# tester.net
KiCad netlist of a schematic drawn in EAGLE
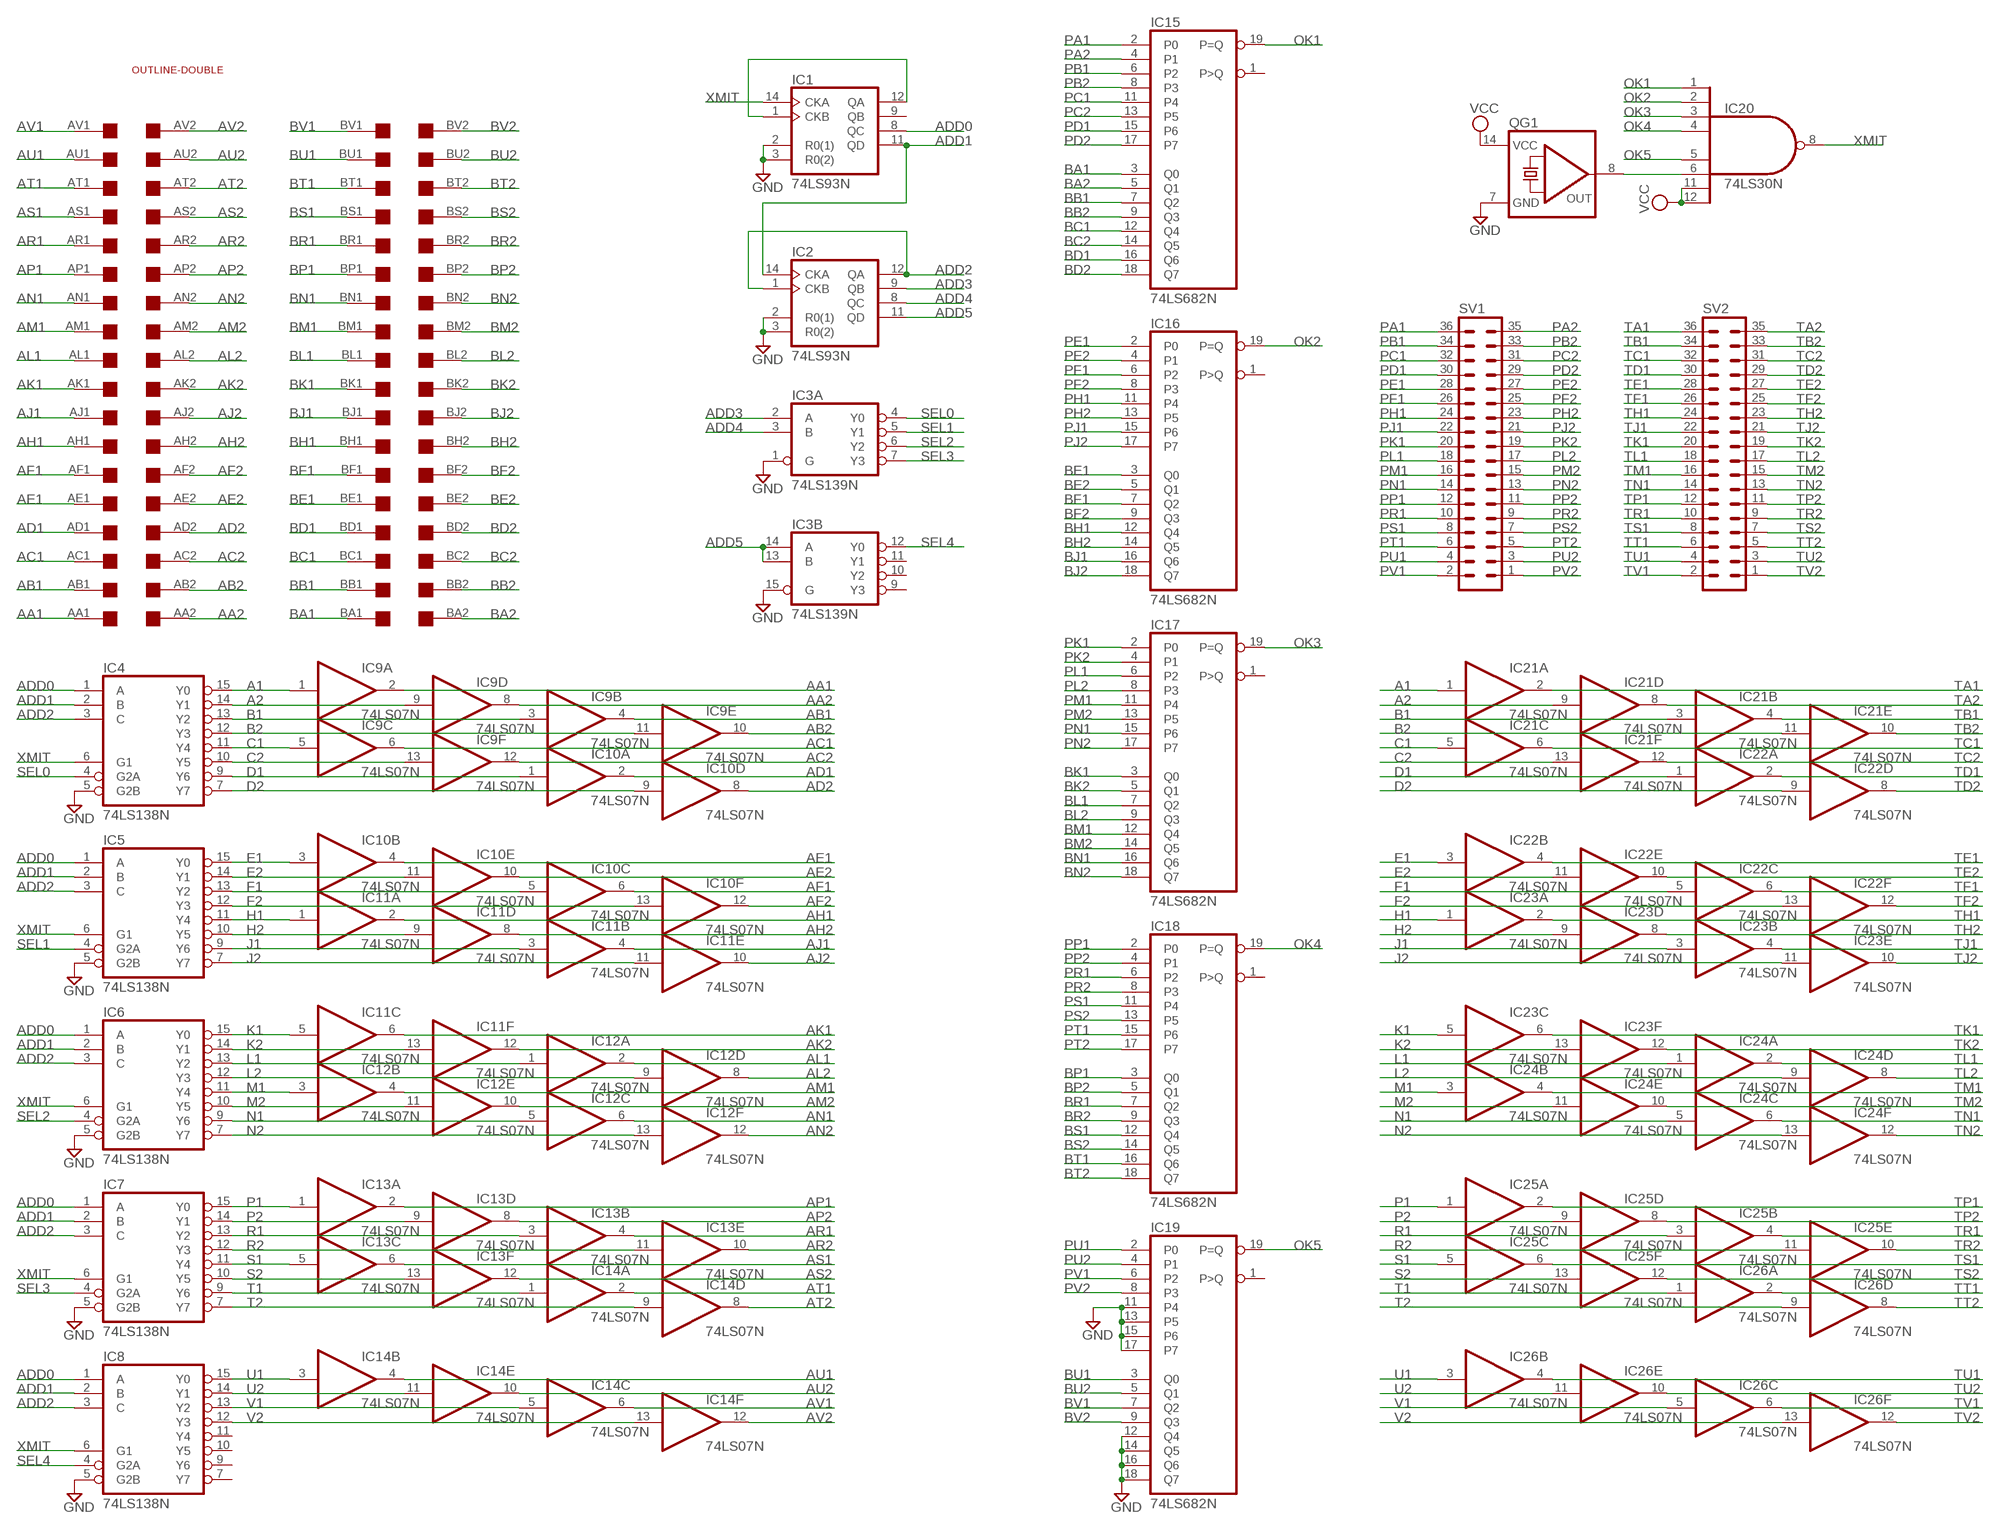
[diagram p0: schematic, sheet 1]

(export (version "E")
  (design (tool "Eeschema 10.0.6"))
  (components
    (comp (ref "IC1")
      (value "74LS93N")
      (footprint "eagle-import:DIL14")
      (libsource (lib "eagle-import") (part "7493NLS"))
    )
    (comp (ref "IC2")
      (value "74LS93N")
      (footprint "eagle-import:DIL14")
      (libsource (lib "eagle-import") (part "7493NLS"))
    )
    (comp (ref "IC3")
      (value "74LS139N")
      (footprint "eagle-import:DIL16")
      (libsource (lib "eagle-import") (part "74139NLS"))
    )
    (comp (ref "IC4")
      (value "74LS138N")
      (footprint "eagle-import:DIL16")
      (libsource (lib "eagle-import") (part "74138NLS"))
    )
    (comp (ref "IC5")
      (value "74LS138N")
      (footprint "eagle-import:DIL16")
      (libsource (lib "eagle-import") (part "74138NLS"))
    )
    (comp (ref "IC6")
      (value "74LS138N")
      (footprint "eagle-import:DIL16")
      (libsource (lib "eagle-import") (part "74138NLS"))
    )
    (comp (ref "IC7")
      (value "74LS138N")
      (footprint "eagle-import:DIL16")
      (libsource (lib "eagle-import") (part "74138NLS"))
    )
    (comp (ref "IC8")
      (value "74LS138N")
      (footprint "eagle-import:DIL16")
      (libsource (lib "eagle-import") (part "74138NLS"))
    )
    (comp (ref "IC9")
      (value "74LS07N")
      (footprint "eagle-import:DIL14")
      (libsource (lib "eagle-import") (part "7407NLS"))
    )
    (comp (ref "IC10")
      (value "74LS07N")
      (footprint "eagle-import:DIL14")
      (libsource (lib "eagle-import") (part "7407NLS"))
    )
    (comp (ref "IC11")
      (value "74LS07N")
      (footprint "eagle-import:DIL14")
      (libsource (lib "eagle-import") (part "7407NLS"))
    )
    (comp (ref "IC12")
      (value "74LS07N")
      (footprint "eagle-import:DIL14")
      (libsource (lib "eagle-import") (part "7407NLS"))
    )
    (comp (ref "IC13")
      (value "74LS07N")
      (footprint "eagle-import:DIL14")
      (libsource (lib "eagle-import") (part "7407NLS"))
    )
    (comp (ref "IC14")
      (value "74LS07N")
      (footprint "eagle-import:DIL14")
      (libsource (lib "eagle-import") (part "7407NLS"))
    )
    (comp (ref "IC15")
      (value "74LS682N")
      (footprint "eagle-import:DIL20")
      (libsource (lib "eagle-import") (part "74682NLS"))
    )
    (comp (ref "IC16")
      (value "74LS682N")
      (footprint "eagle-import:DIL20")
      (libsource (lib "eagle-import") (part "74682NLS"))
    )
    (comp (ref "IC17")
      (value "74LS682N")
      (footprint "eagle-import:DIL20")
      (libsource (lib "eagle-import") (part "74682NLS"))
    )
    (comp (ref "IC18")
      (value "74LS682N")
      (footprint "eagle-import:DIL20")
      (libsource (lib "eagle-import") (part "74682NLS"))
    )
    (comp (ref "IC19")
      (value "74LS682N")
      (footprint "eagle-import:DIL20")
      (libsource (lib "eagle-import") (part "74682NLS"))
    )
    (comp (ref "IC20")
      (value "74LS30N")
      (footprint "eagle-import:DIL14")
      (libsource (lib "eagle-import") (part "7430NLS"))
    )
    (comp (ref "IC21")
      (value "74LS07N")
      (footprint "eagle-import:DIL14")
      (libsource (lib "eagle-import") (part "7407NLS"))
    )
    (comp (ref "IC22")
      (value "74LS07N")
      (footprint "eagle-import:DIL14")
      (libsource (lib "eagle-import") (part "7407NLS"))
    )
    (comp (ref "IC23")
      (value "74LS07N")
      (footprint "eagle-import:DIL14")
      (libsource (lib "eagle-import") (part "7407NLS"))
    )
    (comp (ref "IC24")
      (value "74LS07N")
      (footprint "eagle-import:DIL14")
      (libsource (lib "eagle-import") (part "7407NLS"))
    )
    (comp (ref "IC25")
      (value "74LS07N")
      (footprint "eagle-import:DIL14")
      (libsource (lib "eagle-import") (part "7407NLS"))
    )
    (comp (ref "IC26")
      (value "74LS07N")
      (footprint "eagle-import:DIL14")
      (libsource (lib "eagle-import") (part "7407NLS"))
    )
    (comp (ref "QG1")
      (value "QG5860")
      (footprint "eagle-import:DIL14S")
      (libsource (lib "eagle-import") (part "QG5860"))
    )
    (comp (ref "SV1")
      (value "MA18-2")
      (footprint "eagle-import:MA18-2")
      (libsource (lib "eagle-import") (part "MA18-2"))
    )
    (comp (ref "SV2")
      (value "MA18-2")
      (footprint "eagle-import:MA18-2")
      (libsource (lib "eagle-import") (part "MA18-2"))
    )
    (comp (ref "U$1")
      (value "DOUBLE")
      (footprint "eagle-import:EDGE-CON4")
      (libsource (lib "eagle-import") (part "DOUBLE"))
    )
    (comp (ref "U$2")
      (value "OUTLINE-DOUBLE")
      (footprint "eagle-import:DOUBLE")
      (libsource (lib "eagle-import") (part "OUTLINE-DOUBLE"))
    )
  )
  (nets
    (net (code "1") (name "/A1") (class "Default")
      (node (ref "IC21") (pin "1") (pinfunction "I_1") (pintype "input"))
      (node (ref "IC4") (pin "15") (pinfunction "Y0_15") (pintype "output"))
      (node (ref "IC9") (pin "1") (pinfunction "I_1") (pintype "input"))
    )
    (net (code "2") (name "/A2") (class "Default")
      (node (ref "IC21") (pin "9") (pinfunction "I_9") (pintype "input"))
      (node (ref "IC4") (pin "14") (pinfunction "Y1_14") (pintype "output"))
      (node (ref "IC9") (pin "9") (pinfunction "I_9") (pintype "input"))
    )
    (net (code "3") (name "/AA1") (class "Default")
      (node (ref "IC9") (pin "2") (pinfunction "O_2") (pintype "open_collector"))
      (node (ref "U$1") (pin "AA1") (pinfunction "1_AA1") (pintype "bidirectional"))
    )
    (net (code "4") (name "/AA2") (class "Default")
      (node (ref "IC9") (pin "8") (pinfunction "O_8") (pintype "open_collector"))
      (node (ref "U$1") (pin "AA2") (pinfunction "1_AA2") (pintype "bidirectional"))
    )
    (net (code "5") (name "/AB1") (class "Default")
      (node (ref "IC9") (pin "4") (pinfunction "O_4") (pintype "open_collector"))
      (node (ref "U$1") (pin "AB1") (pinfunction "1_AB1") (pintype "bidirectional"))
    )
    (net (code "6") (name "/AB2") (class "Default")
      (node (ref "IC9") (pin "10") (pinfunction "O_10") (pintype "open_collector"))
      (node (ref "U$1") (pin "AB2") (pinfunction "1_AB2") (pintype "bidirectional"))
    )
    (net (code "7") (name "/AC1") (class "Default")
      (node (ref "IC9") (pin "6") (pinfunction "O_6") (pintype "open_collector"))
      (node (ref "U$1") (pin "AC1") (pinfunction "1_AC1") (pintype "bidirectional"))
    )
    (net (code "8") (name "/AC2") (class "Default")
      (node (ref "IC9") (pin "12") (pinfunction "O_12") (pintype "open_collector"))
      (node (ref "U$1") (pin "AC2") (pinfunction "1_AC2") (pintype "bidirectional"))
    )
    (net (code "9") (name "/AD1") (class "Default")
      (node (ref "IC10") (pin "2") (pinfunction "O_2") (pintype "open_collector"))
      (node (ref "U$1") (pin "AD1") (pinfunction "1_AD1") (pintype "bidirectional"))
    )
    (net (code "10") (name "/AD2") (class "Default")
      (node (ref "IC10") (pin "8") (pinfunction "O_8") (pintype "open_collector"))
      (node (ref "U$1") (pin "AD2") (pinfunction "1_AD2") (pintype "bidirectional"))
    )
    (net (code "11") (name "/ADD0") (class "Default")
      (node (ref "IC1") (pin "8") (pinfunction "QC_8") (pintype "output"))
      (node (ref "IC4") (pin "1") (pinfunction "A_1") (pintype "input"))
      (node (ref "IC5") (pin "1") (pinfunction "A_1") (pintype "input"))
      (node (ref "IC6") (pin "1") (pinfunction "A_1") (pintype "input"))
      (node (ref "IC7") (pin "1") (pinfunction "A_1") (pintype "input"))
      (node (ref "IC8") (pin "1") (pinfunction "A_1") (pintype "input"))
    )
    (net (code "12") (name "/ADD1") (class "Default")
      (node (ref "IC1") (pin "11") (pinfunction "QD_11") (pintype "output"))
      (node (ref "IC2") (pin "14") (pinfunction "CKA_14") (pintype "input"))
      (node (ref "IC4") (pin "2") (pinfunction "B_2") (pintype "input"))
      (node (ref "IC5") (pin "2") (pinfunction "B_2") (pintype "input"))
      (node (ref "IC6") (pin "2") (pinfunction "B_2") (pintype "input"))
      (node (ref "IC7") (pin "2") (pinfunction "B_2") (pintype "input"))
      (node (ref "IC8") (pin "2") (pinfunction "B_2") (pintype "input"))
    )
    (net (code "13") (name "/ADD2") (class "Default")
      (node (ref "IC2") (pin "1") (pinfunction "CKB_1") (pintype "input"))
      (node (ref "IC2") (pin "12") (pinfunction "QA_12") (pintype "output"))
      (node (ref "IC4") (pin "3") (pinfunction "C_3") (pintype "input"))
      (node (ref "IC5") (pin "3") (pinfunction "C_3") (pintype "input"))
      (node (ref "IC6") (pin "3") (pinfunction "C_3") (pintype "input"))
      (node (ref "IC7") (pin "3") (pinfunction "C_3") (pintype "input"))
      (node (ref "IC8") (pin "3") (pinfunction "C_3") (pintype "input"))
    )
    (net (code "14") (name "/ADD3") (class "Default")
      (node (ref "IC2") (pin "9") (pinfunction "QB_9") (pintype "output"))
      (node (ref "IC3") (pin "2") (pinfunction "A_2") (pintype "input"))
    )
    (net (code "15") (name "/ADD4") (class "Default")
      (node (ref "IC2") (pin "8") (pinfunction "QC_8") (pintype "output"))
      (node (ref "IC3") (pin "3") (pinfunction "B_3") (pintype "input"))
    )
    (net (code "16") (name "/ADD5") (class "Default")
      (node (ref "IC2") (pin "11") (pinfunction "QD_11") (pintype "output"))
      (node (ref "IC3") (pin "13") (pinfunction "B_13") (pintype "input"))
      (node (ref "IC3") (pin "14") (pinfunction "A_14") (pintype "input"))
    )
    (net (code "17") (name "/AE1") (class "Default")
      (node (ref "IC10") (pin "4") (pinfunction "O_4") (pintype "open_collector"))
      (node (ref "U$1") (pin "AE1") (pinfunction "1_AE1") (pintype "bidirectional"))
    )
    (net (code "18") (name "/AE2") (class "Default")
      (node (ref "IC10") (pin "10") (pinfunction "O_10") (pintype "open_collector"))
      (node (ref "U$1") (pin "AE2") (pinfunction "1_AE2") (pintype "bidirectional"))
    )
    (net (code "19") (name "/AF1") (class "Default")
      (node (ref "IC10") (pin "6") (pinfunction "O_6") (pintype "open_collector"))
      (node (ref "U$1") (pin "AF1") (pinfunction "1_AF1") (pintype "bidirectional"))
    )
    (net (code "20") (name "/AF2") (class "Default")
      (node (ref "IC10") (pin "12") (pinfunction "O_12") (pintype "open_collector"))
      (node (ref "U$1") (pin "AF2") (pinfunction "1_AF2") (pintype "bidirectional"))
    )
    (net (code "21") (name "/AH1") (class "Default")
      (node (ref "IC11") (pin "2") (pinfunction "O_2") (pintype "open_collector"))
      (node (ref "U$1") (pin "AH1") (pinfunction "1_AH1") (pintype "bidirectional"))
    )
    (net (code "22") (name "/AH2") (class "Default")
      (node (ref "IC11") (pin "8") (pinfunction "O_8") (pintype "open_collector"))
      (node (ref "U$1") (pin "AH2") (pinfunction "1_AH2") (pintype "bidirectional"))
    )
    (net (code "23") (name "/AJ1") (class "Default")
      (node (ref "IC11") (pin "4") (pinfunction "O_4") (pintype "open_collector"))
      (node (ref "U$1") (pin "AJ1") (pinfunction "1_AJ1") (pintype "bidirectional"))
    )
    (net (code "24") (name "/AJ2") (class "Default")
      (node (ref "IC11") (pin "10") (pinfunction "O_10") (pintype "open_collector"))
      (node (ref "U$1") (pin "AJ2") (pinfunction "1_AJ2") (pintype "bidirectional"))
    )
    (net (code "25") (name "/AK1") (class "Default")
      (node (ref "IC11") (pin "6") (pinfunction "O_6") (pintype "open_collector"))
      (node (ref "U$1") (pin "AK1") (pinfunction "1_AK1") (pintype "bidirectional"))
    )
    (net (code "26") (name "/AK2") (class "Default")
      (node (ref "IC11") (pin "12") (pinfunction "O_12") (pintype "open_collector"))
      (node (ref "U$1") (pin "AK2") (pinfunction "1_AK2") (pintype "bidirectional"))
    )
    (net (code "27") (name "/AL1") (class "Default")
      (node (ref "IC12") (pin "2") (pinfunction "O_2") (pintype "open_collector"))
      (node (ref "U$1") (pin "AL1") (pinfunction "1_AL1") (pintype "bidirectional"))
    )
    (net (code "28") (name "/AL2") (class "Default")
      (node (ref "IC12") (pin "8") (pinfunction "O_8") (pintype "open_collector"))
      (node (ref "U$1") (pin "AL2") (pinfunction "1_AL2") (pintype "bidirectional"))
    )
    (net (code "29") (name "/AM1") (class "Default")
      (node (ref "IC12") (pin "4") (pinfunction "O_4") (pintype "open_collector"))
      (node (ref "U$1") (pin "AM1") (pinfunction "1_AM1") (pintype "bidirectional"))
    )
    (net (code "30") (name "/AM2") (class "Default")
      (node (ref "IC12") (pin "10") (pinfunction "O_10") (pintype "open_collector"))
      (node (ref "U$1") (pin "AM2") (pinfunction "1_AM2") (pintype "bidirectional"))
    )
    (net (code "31") (name "/AN1") (class "Default")
      (node (ref "IC12") (pin "6") (pinfunction "O_6") (pintype "open_collector"))
      (node (ref "U$1") (pin "AN1") (pinfunction "1_AN1") (pintype "bidirectional"))
    )
    (net (code "32") (name "/AN2") (class "Default")
      (node (ref "IC12") (pin "12") (pinfunction "O_12") (pintype "open_collector"))
      (node (ref "U$1") (pin "AN2") (pinfunction "1_AN2") (pintype "bidirectional"))
    )
    (net (code "33") (name "/AP1") (class "Default")
      (node (ref "IC13") (pin "2") (pinfunction "O_2") (pintype "open_collector"))
      (node (ref "U$1") (pin "AP1") (pinfunction "1_AP1") (pintype "bidirectional"))
    )
    (net (code "34") (name "/AP2") (class "Default")
      (node (ref "IC13") (pin "8") (pinfunction "O_8") (pintype "open_collector"))
      (node (ref "U$1") (pin "AP2") (pinfunction "1_AP2") (pintype "bidirectional"))
    )
    (net (code "35") (name "/AR1") (class "Default")
      (node (ref "IC13") (pin "4") (pinfunction "O_4") (pintype "open_collector"))
      (node (ref "U$1") (pin "AR1") (pinfunction "1_AR1") (pintype "bidirectional"))
    )
    (net (code "36") (name "/AR2") (class "Default")
      (node (ref "IC13") (pin "10") (pinfunction "O_10") (pintype "open_collector"))
      (node (ref "U$1") (pin "AR2") (pinfunction "1_AR2") (pintype "bidirectional"))
    )
    (net (code "37") (name "/AS1") (class "Default")
      (node (ref "IC13") (pin "6") (pinfunction "O_6") (pintype "open_collector"))
      (node (ref "U$1") (pin "AS1") (pinfunction "1_AS1") (pintype "bidirectional"))
    )
    (net (code "38") (name "/AS2") (class "Default")
      (node (ref "IC13") (pin "12") (pinfunction "O_12") (pintype "open_collector"))
      (node (ref "U$1") (pin "AS2") (pinfunction "1_AS2") (pintype "bidirectional"))
    )
    (net (code "39") (name "/AT1") (class "Default")
      (node (ref "IC14") (pin "2") (pinfunction "O_2") (pintype "open_collector"))
      (node (ref "U$1") (pin "AT1") (pinfunction "1_AT1") (pintype "bidirectional"))
    )
    (net (code "40") (name "/AT2") (class "Default")
      (node (ref "IC14") (pin "8") (pinfunction "O_8") (pintype "open_collector"))
      (node (ref "U$1") (pin "AT2") (pinfunction "1_AT2") (pintype "bidirectional"))
    )
    (net (code "41") (name "/AU1") (class "Default")
      (node (ref "IC14") (pin "4") (pinfunction "O_4") (pintype "open_collector"))
      (node (ref "U$1") (pin "AU1") (pinfunction "1_AU1") (pintype "bidirectional"))
    )
    (net (code "42") (name "/AU2") (class "Default")
      (node (ref "IC14") (pin "10") (pinfunction "O_10") (pintype "open_collector"))
      (node (ref "U$1") (pin "AU2") (pinfunction "1_AU2") (pintype "bidirectional"))
    )
    (net (code "43") (name "/AV1") (class "Default")
      (node (ref "IC14") (pin "6") (pinfunction "O_6") (pintype "open_collector"))
      (node (ref "U$1") (pin "AV1") (pinfunction "1_AV1") (pintype "bidirectional"))
    )
    (net (code "44") (name "/AV2") (class "Default")
      (node (ref "IC14") (pin "12") (pinfunction "O_12") (pintype "open_collector"))
      (node (ref "U$1") (pin "AV2") (pinfunction "1_AV2") (pintype "bidirectional"))
    )
    (net (code "45") (name "/B1") (class "Default")
      (node (ref "IC21") (pin "3") (pinfunction "I_3") (pintype "input"))
      (node (ref "IC4") (pin "13") (pinfunction "Y2_13") (pintype "output"))
      (node (ref "IC9") (pin "3") (pinfunction "I_3") (pintype "input"))
    )
    (net (code "46") (name "/B2") (class "Default")
      (node (ref "IC21") (pin "11") (pinfunction "I_11") (pintype "input"))
      (node (ref "IC4") (pin "12") (pinfunction "Y3_12") (pintype "output"))
      (node (ref "IC9") (pin "11") (pinfunction "I_11") (pintype "input"))
    )
    (net (code "47") (name "/BA1") (class "Default")
      (node (ref "IC15") (pin "3") (pinfunction "Q0_3") (pintype "input"))
      (node (ref "U$1") (pin "BA1") (pinfunction "1_BA1") (pintype "bidirectional"))
    )
    (net (code "48") (name "/BA2") (class "Default")
      (node (ref "IC15") (pin "5") (pinfunction "Q1_5") (pintype "input"))
      (node (ref "U$1") (pin "BA2") (pinfunction "1_BA2") (pintype "bidirectional"))
    )
    (net (code "49") (name "/BB1") (class "Default")
      (node (ref "IC15") (pin "7") (pinfunction "Q2_7") (pintype "input"))
      (node (ref "U$1") (pin "BB1") (pinfunction "1_BB1") (pintype "bidirectional"))
    )
    (net (code "50") (name "/BB2") (class "Default")
      (node (ref "IC15") (pin "9") (pinfunction "Q3_9") (pintype "input"))
      (node (ref "U$1") (pin "BB2") (pinfunction "1_BB2") (pintype "bidirectional"))
    )
    (net (code "51") (name "/BC1") (class "Default")
      (node (ref "IC15") (pin "12") (pinfunction "Q4_12") (pintype "input"))
      (node (ref "U$1") (pin "BC1") (pinfunction "1_BC1") (pintype "bidirectional"))
    )
    (net (code "52") (name "/BC2") (class "Default")
      (node (ref "IC15") (pin "14") (pinfunction "Q5_14") (pintype "input"))
      (node (ref "U$1") (pin "BC2") (pinfunction "1_BC2") (pintype "bidirectional"))
    )
    (net (code "53") (name "/BD1") (class "Default")
      (node (ref "IC15") (pin "16") (pinfunction "Q6_16") (pintype "input"))
      (node (ref "U$1") (pin "BD1") (pinfunction "1_BD1") (pintype "bidirectional"))
    )
    (net (code "54") (name "/BD2") (class "Default")
      (node (ref "IC15") (pin "18") (pinfunction "Q7_18") (pintype "input"))
      (node (ref "U$1") (pin "BD2") (pinfunction "1_BD2") (pintype "bidirectional"))
    )
    (net (code "55") (name "/BE1") (class "Default")
      (node (ref "IC16") (pin "3") (pinfunction "Q0_3") (pintype "input"))
      (node (ref "U$1") (pin "BE1") (pinfunction "1_BE1") (pintype "bidirectional"))
    )
    (net (code "56") (name "/BE2") (class "Default")
      (node (ref "IC16") (pin "5") (pinfunction "Q1_5") (pintype "input"))
      (node (ref "U$1") (pin "BE2") (pinfunction "1_BE2") (pintype "bidirectional"))
    )
    (net (code "57") (name "/BF1") (class "Default")
      (node (ref "IC16") (pin "7") (pinfunction "Q2_7") (pintype "input"))
      (node (ref "U$1") (pin "BF1") (pinfunction "1_BF1") (pintype "bidirectional"))
    )
    (net (code "58") (name "/BF2") (class "Default")
      (node (ref "IC16") (pin "9") (pinfunction "Q3_9") (pintype "input"))
      (node (ref "U$1") (pin "BF2") (pinfunction "1_BF2") (pintype "bidirectional"))
    )
    (net (code "59") (name "/BH1") (class "Default")
      (node (ref "IC16") (pin "12") (pinfunction "Q4_12") (pintype "input"))
      (node (ref "U$1") (pin "BH1") (pinfunction "1_BH1") (pintype "bidirectional"))
    )
    (net (code "60") (name "/BH2") (class "Default")
      (node (ref "IC16") (pin "14") (pinfunction "Q5_14") (pintype "input"))
      (node (ref "U$1") (pin "BH2") (pinfunction "1_BH2") (pintype "bidirectional"))
    )
    (net (code "61") (name "/BJ1") (class "Default")
      (node (ref "IC16") (pin "16") (pinfunction "Q6_16") (pintype "input"))
      (node (ref "U$1") (pin "BJ1") (pinfunction "1_BJ1") (pintype "bidirectional"))
    )
    (net (code "62") (name "/BJ2") (class "Default")
      (node (ref "IC16") (pin "18") (pinfunction "Q7_18") (pintype "input"))
      (node (ref "U$1") (pin "BJ2") (pinfunction "1_BJ2") (pintype "bidirectional"))
    )
    (net (code "63") (name "/BK1") (class "Default")
      (node (ref "IC17") (pin "3") (pinfunction "Q0_3") (pintype "input"))
      (node (ref "U$1") (pin "BK1") (pinfunction "1_BK1") (pintype "bidirectional"))
    )
    (net (code "64") (name "/BK2") (class "Default")
      (node (ref "IC17") (pin "5") (pinfunction "Q1_5") (pintype "input"))
      (node (ref "U$1") (pin "BK2") (pinfunction "1_BK2") (pintype "bidirectional"))
    )
    (net (code "65") (name "/BL1") (class "Default")
      (node (ref "IC17") (pin "7") (pinfunction "Q2_7") (pintype "input"))
      (node (ref "U$1") (pin "BL1") (pinfunction "1_BL1") (pintype "bidirectional"))
    )
    (net (code "66") (name "/BL2") (class "Default")
      (node (ref "IC17") (pin "9") (pinfunction "Q3_9") (pintype "input"))
      (node (ref "U$1") (pin "BL2") (pinfunction "1_BL2") (pintype "bidirectional"))
    )
    (net (code "67") (name "/BM1") (class "Default")
      (node (ref "IC17") (pin "12") (pinfunction "Q4_12") (pintype "input"))
      (node (ref "U$1") (pin "BM1") (pinfunction "1_BM1") (pintype "bidirectional"))
    )
    (net (code "68") (name "/BM2") (class "Default")
      (node (ref "IC17") (pin "14") (pinfunction "Q5_14") (pintype "input"))
      (node (ref "U$1") (pin "BM2") (pinfunction "1_BM2") (pintype "bidirectional"))
    )
    (net (code "69") (name "/BN1") (class "Default")
      (node (ref "IC17") (pin "16") (pinfunction "Q6_16") (pintype "input"))
      (node (ref "U$1") (pin "BN1") (pinfunction "1_BN1") (pintype "bidirectional"))
    )
    (net (code "70") (name "/BN2") (class "Default")
      (node (ref "IC17") (pin "18") (pinfunction "Q7_18") (pintype "input"))
      (node (ref "U$1") (pin "BN2") (pinfunction "1_BN2") (pintype "bidirectional"))
    )
    (net (code "71") (name "/BP1") (class "Default")
      (node (ref "IC18") (pin "3") (pinfunction "Q0_3") (pintype "input"))
      (node (ref "U$1") (pin "BP1") (pinfunction "1_BP1") (pintype "bidirectional"))
    )
    (net (code "72") (name "/BP2") (class "Default")
      (node (ref "IC18") (pin "5") (pinfunction "Q1_5") (pintype "input"))
      (node (ref "U$1") (pin "BP2") (pinfunction "1_BP2") (pintype "bidirectional"))
    )
    (net (code "73") (name "/BR1") (class "Default")
      (node (ref "IC18") (pin "7") (pinfunction "Q2_7") (pintype "input"))
      (node (ref "U$1") (pin "BR1") (pinfunction "1_BR1") (pintype "bidirectional"))
    )
    (net (code "74") (name "/BR2") (class "Default")
      (node (ref "IC18") (pin "9") (pinfunction "Q3_9") (pintype "input"))
      (node (ref "U$1") (pin "BR2") (pinfunction "1_BR2") (pintype "bidirectional"))
    )
    (net (code "75") (name "/BS1") (class "Default")
      (node (ref "IC18") (pin "12") (pinfunction "Q4_12") (pintype "input"))
      (node (ref "U$1") (pin "BS1") (pinfunction "1_BS1") (pintype "bidirectional"))
    )
    (net (code "76") (name "/BS2") (class "Default")
      (node (ref "IC18") (pin "14") (pinfunction "Q5_14") (pintype "input"))
      (node (ref "U$1") (pin "BS2") (pinfunction "1_BS2") (pintype "bidirectional"))
    )
    (net (code "77") (name "/BT1") (class "Default")
      (node (ref "IC18") (pin "16") (pinfunction "Q6_16") (pintype "input"))
      (node (ref "U$1") (pin "BT1") (pinfunction "1_BT1") (pintype "bidirectional"))
    )
    (net (code "78") (name "/BT2") (class "Default")
      (node (ref "IC18") (pin "18") (pinfunction "Q7_18") (pintype "input"))
      (node (ref "U$1") (pin "BT2") (pinfunction "1_BT2") (pintype "bidirectional"))
    )
    (net (code "79") (name "/BU1") (class "Default")
      (node (ref "IC19") (pin "3") (pinfunction "Q0_3") (pintype "input"))
      (node (ref "U$1") (pin "BU1") (pinfunction "1_BU1") (pintype "bidirectional"))
    )
    (net (code "80") (name "/BU2") (class "Default")
      (node (ref "IC19") (pin "5") (pinfunction "Q1_5") (pintype "input"))
      (node (ref "U$1") (pin "BU2") (pinfunction "1_BU2") (pintype "bidirectional"))
    )
    (net (code "81") (name "/BV1") (class "Default")
      (node (ref "IC19") (pin "7") (pinfunction "Q2_7") (pintype "input"))
      (node (ref "U$1") (pin "BV1") (pinfunction "1_BV1") (pintype "bidirectional"))
    )
    (net (code "82") (name "/BV2") (class "Default")
      (node (ref "IC19") (pin "9") (pinfunction "Q3_9") (pintype "input"))
      (node (ref "U$1") (pin "BV2") (pinfunction "1_BV2") (pintype "bidirectional"))
    )
    (net (code "83") (name "/C1") (class "Default")
      (node (ref "IC21") (pin "5") (pinfunction "I_5") (pintype "input"))
      (node (ref "IC4") (pin "11") (pinfunction "Y4_11") (pintype "output"))
      (node (ref "IC9") (pin "5") (pinfunction "I_5") (pintype "input"))
    )
    (net (code "84") (name "/C2") (class "Default")
      (node (ref "IC21") (pin "13") (pinfunction "I_13") (pintype "input"))
      (node (ref "IC4") (pin "10") (pinfunction "Y5_10") (pintype "output"))
      (node (ref "IC9") (pin "13") (pinfunction "I_13") (pintype "input"))
    )
    (net (code "85") (name "/D1") (class "Default")
      (node (ref "IC10") (pin "1") (pinfunction "I_1") (pintype "input"))
      (node (ref "IC22") (pin "1") (pinfunction "I_1") (pintype "input"))
      (node (ref "IC4") (pin "9") (pinfunction "Y6_9") (pintype "output"))
    )
    (net (code "86") (name "/D2") (class "Default")
      (node (ref "IC10") (pin "9") (pinfunction "I_9") (pintype "input"))
      (node (ref "IC22") (pin "9") (pinfunction "I_9") (pintype "input"))
      (node (ref "IC4") (pin "7") (pinfunction "Y7_7") (pintype "output"))
    )
    (net (code "87") (name "/E1") (class "Default")
      (node (ref "IC10") (pin "3") (pinfunction "I_3") (pintype "input"))
      (node (ref "IC22") (pin "3") (pinfunction "I_3") (pintype "input"))
      (node (ref "IC5") (pin "15") (pinfunction "Y0_15") (pintype "output"))
    )
    (net (code "88") (name "/E2") (class "Default")
      (node (ref "IC10") (pin "11") (pinfunction "I_11") (pintype "input"))
      (node (ref "IC22") (pin "11") (pinfunction "I_11") (pintype "input"))
      (node (ref "IC5") (pin "14") (pinfunction "Y1_14") (pintype "output"))
    )
    (net (code "89") (name "/F1") (class "Default")
      (node (ref "IC10") (pin "5") (pinfunction "I_5") (pintype "input"))
      (node (ref "IC22") (pin "5") (pinfunction "I_5") (pintype "input"))
      (node (ref "IC5") (pin "13") (pinfunction "Y2_13") (pintype "output"))
    )
    (net (code "90") (name "/F2") (class "Default")
      (node (ref "IC10") (pin "13") (pinfunction "I_13") (pintype "input"))
      (node (ref "IC22") (pin "13") (pinfunction "I_13") (pintype "input"))
      (node (ref "IC5") (pin "12") (pinfunction "Y3_12") (pintype "output"))
    )
    (net (code "91") (name "/H1") (class "Default")
      (node (ref "IC11") (pin "1") (pinfunction "I_1") (pintype "input"))
      (node (ref "IC23") (pin "1") (pinfunction "I_1") (pintype "input"))
      (node (ref "IC5") (pin "11") (pinfunction "Y4_11") (pintype "output"))
    )
    (net (code "92") (name "/H2") (class "Default")
      (node (ref "IC11") (pin "9") (pinfunction "I_9") (pintype "input"))
      (node (ref "IC23") (pin "9") (pinfunction "I_9") (pintype "input"))
      (node (ref "IC5") (pin "10") (pinfunction "Y5_10") (pintype "output"))
    )
    (net (code "93") (name "/J1") (class "Default")
      (node (ref "IC11") (pin "3") (pinfunction "I_3") (pintype "input"))
      (node (ref "IC23") (pin "3") (pinfunction "I_3") (pintype "input"))
      (node (ref "IC5") (pin "9") (pinfunction "Y6_9") (pintype "output"))
    )
    (net (code "94") (name "/J2") (class "Default")
      (node (ref "IC11") (pin "11") (pinfunction "I_11") (pintype "input"))
      (node (ref "IC23") (pin "11") (pinfunction "I_11") (pintype "input"))
      (node (ref "IC5") (pin "7") (pinfunction "Y7_7") (pintype "output"))
    )
    (net (code "95") (name "/K1") (class "Default")
      (node (ref "IC11") (pin "5") (pinfunction "I_5") (pintype "input"))
      (node (ref "IC23") (pin "5") (pinfunction "I_5") (pintype "input"))
      (node (ref "IC6") (pin "15") (pinfunction "Y0_15") (pintype "output"))
    )
    (net (code "96") (name "/K2") (class "Default")
      (node (ref "IC11") (pin "13") (pinfunction "I_13") (pintype "input"))
      (node (ref "IC23") (pin "13") (pinfunction "I_13") (pintype "input"))
      (node (ref "IC6") (pin "14") (pinfunction "Y1_14") (pintype "output"))
    )
    (net (code "97") (name "/L1") (class "Default")
      (node (ref "IC12") (pin "1") (pinfunction "I_1") (pintype "input"))
      (node (ref "IC24") (pin "1") (pinfunction "I_1") (pintype "input"))
      (node (ref "IC6") (pin "13") (pinfunction "Y2_13") (pintype "output"))
    )
    (net (code "98") (name "/L2") (class "Default")
      (node (ref "IC12") (pin "9") (pinfunction "I_9") (pintype "input"))
      (node (ref "IC24") (pin "9") (pinfunction "I_9") (pintype "input"))
      (node (ref "IC6") (pin "12") (pinfunction "Y3_12") (pintype "output"))
    )
    (net (code "99") (name "/M1") (class "Default")
      (node (ref "IC12") (pin "3") (pinfunction "I_3") (pintype "input"))
      (node (ref "IC24") (pin "3") (pinfunction "I_3") (pintype "input"))
      (node (ref "IC6") (pin "11") (pinfunction "Y4_11") (pintype "output"))
    )
    (net (code "100") (name "/M2") (class "Default")
      (node (ref "IC12") (pin "11") (pinfunction "I_11") (pintype "input"))
      (node (ref "IC24") (pin "11") (pinfunction "I_11") (pintype "input"))
      (node (ref "IC6") (pin "10") (pinfunction "Y5_10") (pintype "output"))
    )
    (net (code "101") (name "/N1") (class "Default")
      (node (ref "IC12") (pin "5") (pinfunction "I_5") (pintype "input"))
      (node (ref "IC24") (pin "5") (pinfunction "I_5") (pintype "input"))
      (node (ref "IC6") (pin "9") (pinfunction "Y6_9") (pintype "output"))
    )
    (net (code "102") (name "/N2") (class "Default")
      (node (ref "IC12") (pin "13") (pinfunction "I_13") (pintype "input"))
      (node (ref "IC24") (pin "13") (pinfunction "I_13") (pintype "input"))
      (node (ref "IC6") (pin "7") (pinfunction "Y7_7") (pintype "output"))
    )
    (net (code "103") (name "/OK1") (class "Default")
      (node (ref "IC15") (pin "19") (pinfunction "P=Q_19") (pintype "output"))
      (node (ref "IC20") (pin "1") (pinfunction "I0_1") (pintype "input"))
    )
    (net (code "104") (name "/OK2") (class "Default")
      (node (ref "IC16") (pin "19") (pinfunction "P=Q_19") (pintype "output"))
      (node (ref "IC20") (pin "2") (pinfunction "I1_2") (pintype "input"))
    )
    (net (code "105") (name "/OK3") (class "Default")
      (node (ref "IC17") (pin "19") (pinfunction "P=Q_19") (pintype "output"))
      (node (ref "IC20") (pin "3") (pinfunction "I2_3") (pintype "input"))
    )
    (net (code "106") (name "/OK4") (class "Default")
      (node (ref "IC18") (pin "19") (pinfunction "P=Q_19") (pintype "output"))
      (node (ref "IC20") (pin "4") (pinfunction "I3_4") (pintype "input"))
    )
    (net (code "107") (name "/OK5") (class "Default")
      (node (ref "IC19") (pin "19") (pinfunction "P=Q_19") (pintype "output"))
      (node (ref "IC20") (pin "5") (pinfunction "I4_5") (pintype "input"))
    )
    (net (code "108") (name "/P1") (class "Default")
      (node (ref "IC13") (pin "1") (pinfunction "I_1") (pintype "input"))
      (node (ref "IC25") (pin "1") (pinfunction "I_1") (pintype "input"))
      (node (ref "IC7") (pin "15") (pinfunction "Y0_15") (pintype "output"))
    )
    (net (code "109") (name "/P2") (class "Default")
      (node (ref "IC13") (pin "9") (pinfunction "I_9") (pintype "input"))
      (node (ref "IC25") (pin "9") (pinfunction "I_9") (pintype "input"))
      (node (ref "IC7") (pin "14") (pinfunction "Y1_14") (pintype "output"))
    )
    (net (code "110") (name "/PA1") (class "Default")
      (node (ref "IC15") (pin "2") (pinfunction "P0_2") (pintype "input"))
      (node (ref "SV1") (pin "36") (pinfunction "36_36") (pintype "passive"))
    )
    (net (code "111") (name "/PA2") (class "Default")
      (node (ref "IC15") (pin "4") (pinfunction "P1_4") (pintype "input"))
      (node (ref "SV1") (pin "35") (pinfunction "35_35") (pintype "passive"))
    )
    (net (code "112") (name "/PB1") (class "Default")
      (node (ref "IC15") (pin "6") (pinfunction "P2_6") (pintype "input"))
      (node (ref "SV1") (pin "34") (pinfunction "34_34") (pintype "passive"))
    )
    (net (code "113") (name "/PB2") (class "Default")
      (node (ref "IC15") (pin "8") (pinfunction "P3_8") (pintype "input"))
      (node (ref "SV1") (pin "33") (pinfunction "33_33") (pintype "passive"))
    )
    (net (code "114") (name "/PC1") (class "Default")
      (node (ref "IC15") (pin "11") (pinfunction "P4_11") (pintype "input"))
      (node (ref "SV1") (pin "32") (pinfunction "32_32") (pintype "passive"))
    )
    (net (code "115") (name "/PC2") (class "Default")
      (node (ref "IC15") (pin "13") (pinfunction "P5_13") (pintype "input"))
      (node (ref "SV1") (pin "31") (pinfunction "31_31") (pintype "passive"))
    )
    (net (code "116") (name "/PD1") (class "Default")
      (node (ref "IC15") (pin "15") (pinfunction "P6_15") (pintype "input"))
      (node (ref "SV1") (pin "30") (pinfunction "30_30") (pintype "passive"))
    )
    (net (code "117") (name "/PD2") (class "Default")
      (node (ref "IC15") (pin "17") (pinfunction "P7_17") (pintype "input"))
      (node (ref "SV1") (pin "29") (pinfunction "29_29") (pintype "passive"))
    )
    (net (code "118") (name "/PE1") (class "Default")
      (node (ref "IC16") (pin "2") (pinfunction "P0_2") (pintype "input"))
      (node (ref "SV1") (pin "28") (pinfunction "28_28") (pintype "passive"))
    )
    (net (code "119") (name "/PE2") (class "Default")
      (node (ref "IC16") (pin "4") (pinfunction "P1_4") (pintype "input"))
      (node (ref "SV1") (pin "27") (pinfunction "27_27") (pintype "passive"))
    )
    (net (code "120") (name "/PF1") (class "Default")
      (node (ref "IC16") (pin "6") (pinfunction "P2_6") (pintype "input"))
      (node (ref "SV1") (pin "26") (pinfunction "26_26") (pintype "passive"))
    )
    (net (code "121") (name "/PF2") (class "Default")
      (node (ref "IC16") (pin "8") (pinfunction "P3_8") (pintype "input"))
      (node (ref "SV1") (pin "25") (pinfunction "25_25") (pintype "passive"))
    )
    (net (code "122") (name "/PH1") (class "Default")
      (node (ref "IC16") (pin "11") (pinfunction "P4_11") (pintype "input"))
      (node (ref "SV1") (pin "24") (pinfunction "24_24") (pintype "passive"))
    )
    (net (code "123") (name "/PH2") (class "Default")
      (node (ref "IC16") (pin "13") (pinfunction "P5_13") (pintype "input"))
      (node (ref "SV1") (pin "23") (pinfunction "23_23") (pintype "passive"))
    )
    (net (code "124") (name "/PJ1") (class "Default")
      (node (ref "IC16") (pin "15") (pinfunction "P6_15") (pintype "input"))
      (node (ref "SV1") (pin "22") (pinfunction "22_22") (pintype "passive"))
    )
    (net (code "125") (name "/PJ2") (class "Default")
      (node (ref "IC16") (pin "17") (pinfunction "P7_17") (pintype "input"))
      (node (ref "SV1") (pin "21") (pinfunction "21_21") (pintype "passive"))
    )
    (net (code "126") (name "/PK1") (class "Default")
      (node (ref "IC17") (pin "2") (pinfunction "P0_2") (pintype "input"))
      (node (ref "SV1") (pin "20") (pinfunction "20_20") (pintype "passive"))
    )
    (net (code "127") (name "/PK2") (class "Default")
      (node (ref "IC17") (pin "4") (pinfunction "P1_4") (pintype "input"))
      (node (ref "SV1") (pin "19") (pinfunction "19_19") (pintype "passive"))
    )
    (net (code "128") (name "/PL1") (class "Default")
      (node (ref "IC17") (pin "6") (pinfunction "P2_6") (pintype "input"))
      (node (ref "SV1") (pin "18") (pinfunction "18_18") (pintype "passive"))
    )
    (net (code "129") (name "/PL2") (class "Default")
      (node (ref "IC17") (pin "8") (pinfunction "P3_8") (pintype "input"))
      (node (ref "SV1") (pin "17") (pinfunction "17_17") (pintype "passive"))
    )
    (net (code "130") (name "/PM1") (class "Default")
      (node (ref "IC17") (pin "11") (pinfunction "P4_11") (pintype "input"))
      (node (ref "SV1") (pin "16") (pinfunction "16_16") (pintype "passive"))
    )
    (net (code "131") (name "/PM2") (class "Default")
      (node (ref "IC17") (pin "13") (pinfunction "P5_13") (pintype "input"))
      (node (ref "SV1") (pin "15") (pinfunction "15_15") (pintype "passive"))
    )
    (net (code "132") (name "/PN1") (class "Default")
      (node (ref "IC17") (pin "15") (pinfunction "P6_15") (pintype "input"))
      (node (ref "SV1") (pin "14") (pinfunction "14_14") (pintype "passive"))
    )
    (net (code "133") (name "/PN2") (class "Default")
      (node (ref "IC17") (pin "17") (pinfunction "P7_17") (pintype "input"))
      (node (ref "SV1") (pin "13") (pinfunction "13_13") (pintype "passive"))
    )
    (net (code "134") (name "/PP1") (class "Default")
      (node (ref "IC18") (pin "2") (pinfunction "P0_2") (pintype "input"))
      (node (ref "SV1") (pin "12") (pinfunction "12_12") (pintype "passive"))
    )
    (net (code "135") (name "/PP2") (class "Default")
      (node (ref "IC18") (pin "4") (pinfunction "P1_4") (pintype "input"))
      (node (ref "SV1") (pin "11") (pinfunction "11_11") (pintype "passive"))
    )
    (net (code "136") (name "/PR1") (class "Default")
      (node (ref "IC18") (pin "6") (pinfunction "P2_6") (pintype "input"))
      (node (ref "SV1") (pin "10") (pinfunction "10_10") (pintype "passive"))
    )
    (net (code "137") (name "/PR2") (class "Default")
      (node (ref "IC18") (pin "8") (pinfunction "P3_8") (pintype "input"))
      (node (ref "SV1") (pin "9") (pinfunction "9_9") (pintype "passive"))
    )
    (net (code "138") (name "/PS1") (class "Default")
      (node (ref "IC18") (pin "11") (pinfunction "P4_11") (pintype "input"))
      (node (ref "SV1") (pin "8") (pinfunction "8_8") (pintype "passive"))
    )
    (net (code "139") (name "/PS2") (class "Default")
      (node (ref "IC18") (pin "13") (pinfunction "P5_13") (pintype "input"))
      (node (ref "SV1") (pin "7") (pinfunction "7_7") (pintype "passive"))
    )
    (net (code "140") (name "/PT1") (class "Default")
      (node (ref "IC18") (pin "15") (pinfunction "P6_15") (pintype "input"))
      (node (ref "SV1") (pin "6") (pinfunction "6_6") (pintype "passive"))
    )
    (net (code "141") (name "/PT2") (class "Default")
      (node (ref "IC18") (pin "17") (pinfunction "P7_17") (pintype "input"))
      (node (ref "SV1") (pin "5") (pinfunction "5_5") (pintype "passive"))
    )
    (net (code "142") (name "/PU1") (class "Default")
      (node (ref "IC19") (pin "2") (pinfunction "P0_2") (pintype "input"))
      (node (ref "SV1") (pin "4") (pinfunction "4_4") (pintype "passive"))
    )
    (net (code "143") (name "/PU2") (class "Default")
      (node (ref "IC19") (pin "4") (pinfunction "P1_4") (pintype "input"))
      (node (ref "SV1") (pin "3") (pinfunction "3_3") (pintype "passive"))
    )
    (net (code "144") (name "/PV1") (class "Default")
      (node (ref "IC19") (pin "6") (pinfunction "P2_6") (pintype "input"))
      (node (ref "SV1") (pin "2") (pinfunction "2_2") (pintype "passive"))
    )
    (net (code "145") (name "/PV2") (class "Default")
      (node (ref "IC19") (pin "8") (pinfunction "P3_8") (pintype "input"))
      (node (ref "SV1") (pin "1") (pinfunction "1_1") (pintype "passive"))
    )
    (net (code "146") (name "/R1") (class "Default")
      (node (ref "IC13") (pin "3") (pinfunction "I_3") (pintype "input"))
      (node (ref "IC25") (pin "3") (pinfunction "I_3") (pintype "input"))
      (node (ref "IC7") (pin "13") (pinfunction "Y2_13") (pintype "output"))
    )
    (net (code "147") (name "/R2") (class "Default")
      (node (ref "IC13") (pin "11") (pinfunction "I_11") (pintype "input"))
      (node (ref "IC25") (pin "11") (pinfunction "I_11") (pintype "input"))
      (node (ref "IC7") (pin "12") (pinfunction "Y3_12") (pintype "output"))
    )
    (net (code "148") (name "/S1") (class "Default")
      (node (ref "IC13") (pin "5") (pinfunction "I_5") (pintype "input"))
      (node (ref "IC25") (pin "5") (pinfunction "I_5") (pintype "input"))
      (node (ref "IC7") (pin "11") (pinfunction "Y4_11") (pintype "output"))
    )
    (net (code "149") (name "/S2") (class "Default")
      (node (ref "IC13") (pin "13") (pinfunction "I_13") (pintype "input"))
      (node (ref "IC25") (pin "13") (pinfunction "I_13") (pintype "input"))
      (node (ref "IC7") (pin "10") (pinfunction "Y5_10") (pintype "output"))
    )
    (net (code "150") (name "/SEL0") (class "Default")
      (node (ref "IC3") (pin "4") (pinfunction "Y0_4") (pintype "output"))
      (node (ref "IC4") (pin "4") (pinfunction "G2A_4") (pintype "input"))
    )
    (net (code "151") (name "/SEL1") (class "Default")
      (node (ref "IC3") (pin "5") (pinfunction "Y1_5") (pintype "output"))
      (node (ref "IC5") (pin "4") (pinfunction "G2A_4") (pintype "input"))
    )
    (net (code "152") (name "/SEL2") (class "Default")
      (node (ref "IC3") (pin "6") (pinfunction "Y2_6") (pintype "output"))
      (node (ref "IC6") (pin "4") (pinfunction "G2A_4") (pintype "input"))
    )
    (net (code "153") (name "/SEL3") (class "Default")
      (node (ref "IC3") (pin "7") (pinfunction "Y3_7") (pintype "output"))
      (node (ref "IC7") (pin "4") (pinfunction "G2A_4") (pintype "input"))
    )
    (net (code "154") (name "/SEL4") (class "Default")
      (node (ref "IC3") (pin "12") (pinfunction "Y0_12") (pintype "output"))
      (node (ref "IC8") (pin "4") (pinfunction "G2A_4") (pintype "input"))
    )
    (net (code "155") (name "/T1") (class "Default")
      (node (ref "IC14") (pin "1") (pinfunction "I_1") (pintype "input"))
      (node (ref "IC26") (pin "1") (pinfunction "I_1") (pintype "input"))
      (node (ref "IC7") (pin "9") (pinfunction "Y6_9") (pintype "output"))
    )
    (net (code "156") (name "/T2") (class "Default")
      (node (ref "IC14") (pin "9") (pinfunction "I_9") (pintype "input"))
      (node (ref "IC26") (pin "9") (pinfunction "I_9") (pintype "input"))
      (node (ref "IC7") (pin "7") (pinfunction "Y7_7") (pintype "output"))
    )
    (net (code "157") (name "/TA1") (class "Default")
      (node (ref "IC21") (pin "2") (pinfunction "O_2") (pintype "open_collector"))
      (node (ref "SV2") (pin "36") (pinfunction "36_36") (pintype "passive"))
    )
    (net (code "158") (name "/TA2") (class "Default")
      (node (ref "IC21") (pin "8") (pinfunction "O_8") (pintype "open_collector"))
      (node (ref "SV2") (pin "35") (pinfunction "35_35") (pintype "passive"))
    )
    (net (code "159") (name "/TB1") (class "Default")
      (node (ref "IC21") (pin "4") (pinfunction "O_4") (pintype "open_collector"))
      (node (ref "SV2") (pin "34") (pinfunction "34_34") (pintype "passive"))
    )
    (net (code "160") (name "/TB2") (class "Default")
      (node (ref "IC21") (pin "10") (pinfunction "O_10") (pintype "open_collector"))
      (node (ref "SV2") (pin "33") (pinfunction "33_33") (pintype "passive"))
    )
    (net (code "161") (name "/TC1") (class "Default")
      (node (ref "IC21") (pin "6") (pinfunction "O_6") (pintype "open_collector"))
      (node (ref "SV2") (pin "32") (pinfunction "32_32") (pintype "passive"))
    )
    (net (code "162") (name "/TC2") (class "Default")
      (node (ref "IC21") (pin "12") (pinfunction "O_12") (pintype "open_collector"))
      (node (ref "SV2") (pin "31") (pinfunction "31_31") (pintype "passive"))
    )
    (net (code "163") (name "/TD1") (class "Default")
      (node (ref "IC22") (pin "2") (pinfunction "O_2") (pintype "open_collector"))
      (node (ref "SV2") (pin "30") (pinfunction "30_30") (pintype "passive"))
    )
    (net (code "164") (name "/TD2") (class "Default")
      (node (ref "IC22") (pin "8") (pinfunction "O_8") (pintype "open_collector"))
      (node (ref "SV2") (pin "29") (pinfunction "29_29") (pintype "passive"))
    )
    (net (code "165") (name "/TE1") (class "Default")
      (node (ref "IC22") (pin "4") (pinfunction "O_4") (pintype "open_collector"))
      (node (ref "SV2") (pin "28") (pinfunction "28_28") (pintype "passive"))
    )
    (net (code "166") (name "/TE2") (class "Default")
      (node (ref "IC22") (pin "10") (pinfunction "O_10") (pintype "open_collector"))
      (node (ref "SV2") (pin "27") (pinfunction "27_27") (pintype "passive"))
    )
    (net (code "167") (name "/TF1") (class "Default")
      (node (ref "IC22") (pin "6") (pinfunction "O_6") (pintype "open_collector"))
      (node (ref "SV2") (pin "26") (pinfunction "26_26") (pintype "passive"))
    )
    (net (code "168") (name "/TF2") (class "Default")
      (node (ref "IC22") (pin "12") (pinfunction "O_12") (pintype "open_collector"))
      (node (ref "SV2") (pin "25") (pinfunction "25_25") (pintype "passive"))
    )
    (net (code "169") (name "/TH1") (class "Default")
      (node (ref "IC23") (pin "2") (pinfunction "O_2") (pintype "open_collector"))
      (node (ref "SV2") (pin "24") (pinfunction "24_24") (pintype "passive"))
    )
    (net (code "170") (name "/TH2") (class "Default")
      (node (ref "IC23") (pin "8") (pinfunction "O_8") (pintype "open_collector"))
      (node (ref "SV2") (pin "23") (pinfunction "23_23") (pintype "passive"))
    )
    (net (code "171") (name "/TJ1") (class "Default")
      (node (ref "IC23") (pin "4") (pinfunction "O_4") (pintype "open_collector"))
      (node (ref "SV2") (pin "22") (pinfunction "22_22") (pintype "passive"))
    )
    (net (code "172") (name "/TJ2") (class "Default")
      (node (ref "IC23") (pin "10") (pinfunction "O_10") (pintype "open_collector"))
      (node (ref "SV2") (pin "21") (pinfunction "21_21") (pintype "passive"))
    )
    (net (code "173") (name "/TK1") (class "Default")
      (node (ref "IC23") (pin "6") (pinfunction "O_6") (pintype "open_collector"))
      (node (ref "SV2") (pin "20") (pinfunction "20_20") (pintype "passive"))
    )
    (net (code "174") (name "/TK2") (class "Default")
      (node (ref "IC23") (pin "12") (pinfunction "O_12") (pintype "open_collector"))
      (node (ref "SV2") (pin "19") (pinfunction "19_19") (pintype "passive"))
    )
    (net (code "175") (name "/TL1") (class "Default")
      (node (ref "IC24") (pin "2") (pinfunction "O_2") (pintype "open_collector"))
      (node (ref "SV2") (pin "18") (pinfunction "18_18") (pintype "passive"))
    )
    (net (code "176") (name "/TL2") (class "Default")
      (node (ref "IC24") (pin "8") (pinfunction "O_8") (pintype "open_collector"))
      (node (ref "SV2") (pin "17") (pinfunction "17_17") (pintype "passive"))
    )
    (net (code "177") (name "/TM1") (class "Default")
      (node (ref "IC24") (pin "4") (pinfunction "O_4") (pintype "open_collector"))
      (node (ref "SV2") (pin "16") (pinfunction "16_16") (pintype "passive"))
    )
    (net (code "178") (name "/TM2") (class "Default")
      (node (ref "IC24") (pin "10") (pinfunction "O_10") (pintype "open_collector"))
      (node (ref "SV2") (pin "15") (pinfunction "15_15") (pintype "passive"))
    )
    (net (code "179") (name "/TN1") (class "Default")
      (node (ref "IC24") (pin "6") (pinfunction "O_6") (pintype "open_collector"))
      (node (ref "SV2") (pin "14") (pinfunction "14_14") (pintype "passive"))
    )
    (net (code "180") (name "/TN2") (class "Default")
      (node (ref "IC24") (pin "12") (pinfunction "O_12") (pintype "open_collector"))
      (node (ref "SV2") (pin "13") (pinfunction "13_13") (pintype "passive"))
    )
    (net (code "181") (name "/TP1") (class "Default")
      (node (ref "IC25") (pin "2") (pinfunction "O_2") (pintype "open_collector"))
      (node (ref "SV2") (pin "12") (pinfunction "12_12") (pintype "passive"))
    )
    (net (code "182") (name "/TP2") (class "Default")
      (node (ref "IC25") (pin "8") (pinfunction "O_8") (pintype "open_collector"))
      (node (ref "SV2") (pin "11") (pinfunction "11_11") (pintype "passive"))
    )
    (net (code "183") (name "/TR1") (class "Default")
      (node (ref "IC25") (pin "4") (pinfunction "O_4") (pintype "open_collector"))
      (node (ref "SV2") (pin "10") (pinfunction "10_10") (pintype "passive"))
    )
    (net (code "184") (name "/TR2") (class "Default")
      (node (ref "IC25") (pin "10") (pinfunction "O_10") (pintype "open_collector"))
      (node (ref "SV2") (pin "9") (pinfunction "9_9") (pintype "passive"))
    )
    (net (code "185") (name "/TS1") (class "Default")
      (node (ref "IC25") (pin "6") (pinfunction "O_6") (pintype "open_collector"))
      (node (ref "SV2") (pin "8") (pinfunction "8_8") (pintype "passive"))
    )
    (net (code "186") (name "/TS2") (class "Default")
      (node (ref "IC25") (pin "12") (pinfunction "O_12") (pintype "open_collector"))
      (node (ref "SV2") (pin "7") (pinfunction "7_7") (pintype "passive"))
    )
    (net (code "187") (name "/TT1") (class "Default")
      (node (ref "IC26") (pin "2") (pinfunction "O_2") (pintype "open_collector"))
      (node (ref "SV2") (pin "6") (pinfunction "6_6") (pintype "passive"))
    )
    (net (code "188") (name "/TT2") (class "Default")
      (node (ref "IC26") (pin "8") (pinfunction "O_8") (pintype "open_collector"))
      (node (ref "SV2") (pin "5") (pinfunction "5_5") (pintype "passive"))
    )
    (net (code "189") (name "/TU1") (class "Default")
      (node (ref "IC26") (pin "4") (pinfunction "O_4") (pintype "open_collector"))
      (node (ref "SV2") (pin "4") (pinfunction "4_4") (pintype "passive"))
    )
    (net (code "190") (name "/TU2") (class "Default")
      (node (ref "IC26") (pin "10") (pinfunction "O_10") (pintype "open_collector"))
      (node (ref "SV2") (pin "3") (pinfunction "3_3") (pintype "passive"))
    )
    (net (code "191") (name "/TV1") (class "Default")
      (node (ref "IC26") (pin "6") (pinfunction "O_6") (pintype "open_collector"))
      (node (ref "SV2") (pin "2") (pinfunction "2_2") (pintype "passive"))
    )
    (net (code "192") (name "/TV2") (class "Default")
      (node (ref "IC26") (pin "12") (pinfunction "O_12") (pintype "open_collector"))
      (node (ref "SV2") (pin "1") (pinfunction "1_1") (pintype "passive"))
    )
    (net (code "193") (name "/U1") (class "Default")
      (node (ref "IC14") (pin "3") (pinfunction "I_3") (pintype "input"))
      (node (ref "IC26") (pin "3") (pinfunction "I_3") (pintype "input"))
      (node (ref "IC8") (pin "15") (pinfunction "Y0_15") (pintype "output"))
    )
    (net (code "194") (name "/U2") (class "Default")
      (node (ref "IC14") (pin "11") (pinfunction "I_11") (pintype "input"))
      (node (ref "IC26") (pin "11") (pinfunction "I_11") (pintype "input"))
      (node (ref "IC8") (pin "14") (pinfunction "Y1_14") (pintype "output"))
    )
    (net (code "195") (name "/V1") (class "Default")
      (node (ref "IC14") (pin "5") (pinfunction "I_5") (pintype "input"))
      (node (ref "IC26") (pin "5") (pinfunction "I_5") (pintype "input"))
      (node (ref "IC8") (pin "13") (pinfunction "Y2_13") (pintype "output"))
    )
    (net (code "196") (name "/V2") (class "Default")
      (node (ref "IC14") (pin "13") (pinfunction "I_13") (pintype "input"))
      (node (ref "IC26") (pin "13") (pinfunction "I_13") (pintype "input"))
      (node (ref "IC8") (pin "12") (pinfunction "Y3_12") (pintype "output"))
    )
    (net (code "197") (name "/XMIT") (class "Default")
      (node (ref "IC1") (pin "14") (pinfunction "CKA_14") (pintype "input"))
      (node (ref "IC20") (pin "8") (pinfunction "O_8") (pintype "output"))
      (node (ref "IC4") (pin "6") (pinfunction "G1_6") (pintype "input"))
      (node (ref "IC5") (pin "6") (pinfunction "G1_6") (pintype "input"))
      (node (ref "IC6") (pin "6") (pinfunction "G1_6") (pintype "input"))
      (node (ref "IC7") (pin "6") (pinfunction "G1_6") (pintype "input"))
      (node (ref "IC8") (pin "6") (pinfunction "G1_6") (pintype "input"))
    )
    (net (code "198") (name "GND") (class "Default")
      (node (ref "IC1") (pin "2") (pinfunction "R0(1)_2") (pintype "input"))
      (node (ref "IC1") (pin "3") (pinfunction "R0(2)_3") (pintype "input"))
      (node (ref "IC19") (pin "11") (pinfunction "P4_11") (pintype "input"))
      (node (ref "IC19") (pin "12") (pinfunction "Q4_12") (pintype "input"))
      (node (ref "IC19") (pin "13") (pinfunction "P5_13") (pintype "input"))
      (node (ref "IC19") (pin "14") (pinfunction "Q5_14") (pintype "input"))
      (node (ref "IC19") (pin "15") (pinfunction "P6_15") (pintype "input"))
      (node (ref "IC19") (pin "16") (pinfunction "Q6_16") (pintype "input"))
      (node (ref "IC19") (pin "17") (pinfunction "P7_17") (pintype "input"))
      (node (ref "IC19") (pin "18") (pinfunction "Q7_18") (pintype "input"))
      (node (ref "IC2") (pin "2") (pinfunction "R0(1)_2") (pintype "input"))
      (node (ref "IC2") (pin "3") (pinfunction "R0(2)_3") (pintype "input"))
      (node (ref "IC3") (pin "1") (pinfunction "G_1") (pintype "input"))
      (node (ref "IC3") (pin "15") (pinfunction "G_15") (pintype "input"))
      (node (ref "IC4") (pin "5") (pinfunction "G2B_5") (pintype "input"))
      (node (ref "IC5") (pin "5") (pinfunction "G2B_5") (pintype "input"))
      (node (ref "IC6") (pin "5") (pinfunction "G2B_5") (pintype "input"))
      (node (ref "IC7") (pin "5") (pinfunction "G2B_5") (pintype "input"))
      (node (ref "IC8") (pin "5") (pinfunction "G2B_5") (pintype "input"))
      (node (ref "QG1") (pin "7") (pinfunction "GND_7") (pintype "power_in"))
    )
    (net (code "199") (name "Net-(IC1A-CKB)") (class "Default")
      (node (ref "IC1") (pin "1") (pinfunction "CKB_1") (pintype "input"))
      (node (ref "IC1") (pin "12") (pinfunction "QA_12") (pintype "output"))
    )
    (net (code "200") (name "Net-(IC20A-I5)") (class "Default")
      (node (ref "IC20") (pin "6") (pinfunction "I5_6") (pintype "input"))
      (node (ref "QG1") (pin "8") (pinfunction "OUT_8") (pintype "output"))
    )
    (net (code "201") (name "VCC") (class "Default")
      (node (ref "IC20") (pin "11") (pinfunction "I6_11") (pintype "input"))
      (node (ref "IC20") (pin "12") (pinfunction "I7_12") (pintype "input"))
      (node (ref "QG1") (pin "14") (pinfunction "VCC_14") (pintype "power_in"))
    )
    (net (code "202") (name "unconnected-(IC1A-QB-Pad9)") (class "Default")
      (node (ref "IC1") (pin "9") (pinfunction "QB_9") (pintype "output"))
    )
    (net (code "203") (name "unconnected-(IC3B-Y1-Pad11)") (class "Default")
      (node (ref "IC3") (pin "11") (pinfunction "Y1_11") (pintype "output"))
    )
    (net (code "204") (name "unconnected-(IC3B-Y2-Pad10)") (class "Default")
      (node (ref "IC3") (pin "10") (pinfunction "Y2_10") (pintype "output"))
    )
    (net (code "205") (name "unconnected-(IC3B-Y3-Pad9)") (class "Default")
      (node (ref "IC3") (pin "9") (pinfunction "Y3_9") (pintype "output"))
    )
    (net (code "206") (name "unconnected-(IC8A-Y4-Pad11)") (class "Default")
      (node (ref "IC8") (pin "11") (pinfunction "Y4_11") (pintype "output"))
    )
    (net (code "207") (name "unconnected-(IC8A-Y5-Pad10)") (class "Default")
      (node (ref "IC8") (pin "10") (pinfunction "Y5_10") (pintype "output"))
    )
    (net (code "208") (name "unconnected-(IC8A-Y6-Pad9)") (class "Default")
      (node (ref "IC8") (pin "9") (pinfunction "Y6_9") (pintype "output"))
    )
    (net (code "209") (name "unconnected-(IC8A-Y7-Pad7)") (class "Default")
      (node (ref "IC8") (pin "7") (pinfunction "Y7_7") (pintype "output"))
    )
    (net (code "210") (name "unconnected-(IC15A-P>Q-Pad1)") (class "Default")
      (node (ref "IC15") (pin "1") (pinfunction "P>Q_1") (pintype "output"))
    )
    (net (code "211") (name "unconnected-(IC16A-P>Q-Pad1)") (class "Default")
      (node (ref "IC16") (pin "1") (pinfunction "P>Q_1") (pintype "output"))
    )
    (net (code "212") (name "unconnected-(IC17A-P>Q-Pad1)") (class "Default")
      (node (ref "IC17") (pin "1") (pinfunction "P>Q_1") (pintype "output"))
    )
    (net (code "213") (name "unconnected-(IC18A-P>Q-Pad1)") (class "Default")
      (node (ref "IC18") (pin "1") (pinfunction "P>Q_1") (pintype "output"))
    )
    (net (code "214") (name "unconnected-(IC19A-P>Q-Pad1)") (class "Default")
      (node (ref "IC19") (pin "1") (pinfunction "P>Q_1") (pintype "output"))
    )
  )
)
